# door_fan_bell.net
KiCad netlist of a schematic drawn in Altium Designer
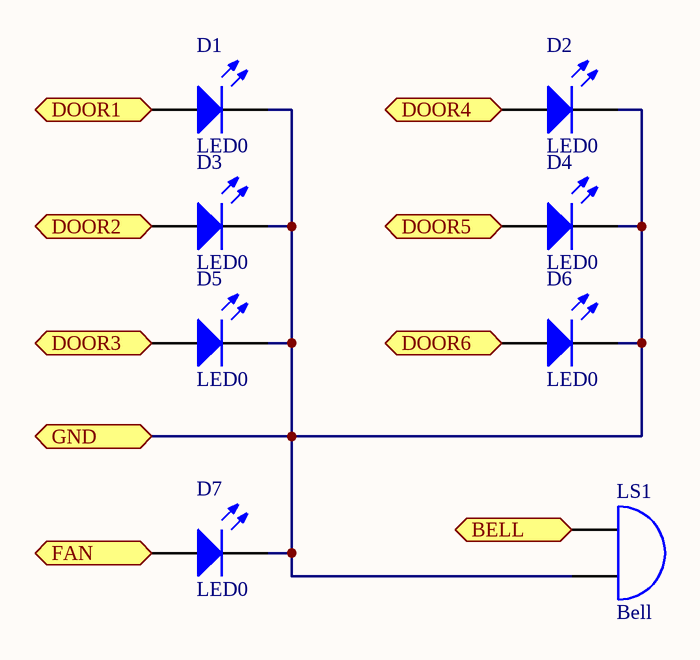
[diagram p0: door_fan_bell.SchDoc]

(export (version "E")
  (design (tool "Eeschema 10.0.6"))
  (components
    (comp (ref "D1")
      (value "LED0")
      (footprint "1206")
      (description "Typical INFRARED GaAs LED")
      (fields (field (name "PUBLISHER") "Altium Limited"))
      (libsource (lib "Miscellaneous Devices") (part "LED0"))
    )
    (comp (ref "D2")
      (value "LED0")
      (footprint "1206")
      (description "Typical INFRARED GaAs LED")
      (fields (field (name "PUBLISHER") "Altium Limited"))
      (libsource (lib "Miscellaneous Devices") (part "LED0"))
    )
    (comp (ref "D3")
      (value "LED0")
      (footprint "1206")
      (description "Typical INFRARED GaAs LED")
      (fields (field (name "PUBLISHER") "Altium Limited"))
      (libsource (lib "Miscellaneous Devices") (part "LED0"))
    )
    (comp (ref "D4")
      (value "LED0")
      (footprint "1206")
      (description "Typical INFRARED GaAs LED")
      (fields (field (name "PUBLISHER") "Altium Limited"))
      (libsource (lib "Miscellaneous Devices") (part "LED0"))
    )
    (comp (ref "D5")
      (value "LED0")
      (footprint "1206")
      (description "Typical INFRARED GaAs LED")
      (fields (field (name "PUBLISHER") "Altium Limited"))
      (libsource (lib "Miscellaneous Devices") (part "LED0"))
    )
    (comp (ref "D6")
      (value "LED0")
      (footprint "1206")
      (description "Typical INFRARED GaAs LED")
      (fields (field (name "PUBLISHER") "Altium Limited"))
      (libsource (lib "Miscellaneous Devices") (part "LED0"))
    )
    (comp (ref "D7")
      (value "LED0")
      (footprint "1206")
      (description "Typical INFRARED GaAs LED")
      (fields (field (name "PUBLISHER") "Altium Limited"))
      (libsource (lib "Miscellaneous Devices") (part "LED0"))
    )
    (comp (ref "LS1")
      (value "Bell")
      (footprint "蜂鸣器")
      (description "Electrical Bell")
      (fields (field (name "PUBLISHER") "Altium Limited"))
      (libsource (lib "Miscellaneous Devices") (part "Bell"))
    )
  )
  (nets
    (net (code "1") (name "/BELL") (class "Default")
      (node (ref "LS1") (pin "1") (pinfunction "A_1") (pintype "passive"))
    )
    (net (code "2") (name "/DOOR1") (class "Default")
      (node (ref "D1") (pin "1") (pinfunction "A_1") (pintype "passive"))
    )
    (net (code "3") (name "/DOOR2") (class "Default")
      (node (ref "D3") (pin "1") (pinfunction "A_1") (pintype "passive"))
    )
    (net (code "4") (name "/DOOR3") (class "Default")
      (node (ref "D5") (pin "1") (pinfunction "A_1") (pintype "passive"))
    )
    (net (code "5") (name "/DOOR4") (class "Default")
      (node (ref "D2") (pin "1") (pinfunction "A_1") (pintype "passive"))
    )
    (net (code "6") (name "/DOOR5") (class "Default")
      (node (ref "D4") (pin "1") (pinfunction "A_1") (pintype "passive"))
    )
    (net (code "7") (name "/DOOR6") (class "Default")
      (node (ref "D6") (pin "1") (pinfunction "A_1") (pintype "passive"))
    )
    (net (code "8") (name "/FAN") (class "Default")
      (node (ref "D7") (pin "1") (pinfunction "A_1") (pintype "passive"))
    )
    (net (code "9") (name "/GND") (class "Default")
      (node (ref "D1") (pin "2") (pinfunction "K_2") (pintype "passive"))
      (node (ref "D2") (pin "2") (pinfunction "K_2") (pintype "passive"))
      (node (ref "D3") (pin "2") (pinfunction "K_2") (pintype "passive"))
      (node (ref "D4") (pin "2") (pinfunction "K_2") (pintype "passive"))
      (node (ref "D5") (pin "2") (pinfunction "K_2") (pintype "passive"))
      (node (ref "D6") (pin "2") (pinfunction "K_2") (pintype "passive"))
      (node (ref "D7") (pin "2") (pinfunction "K_2") (pintype "passive"))
      (node (ref "LS1") (pin "2") (pinfunction "B_2") (pintype "passive"))
    )
  )
)
